# Connectors.net
KiCad netlist of a schematic drawn in Altium Designer
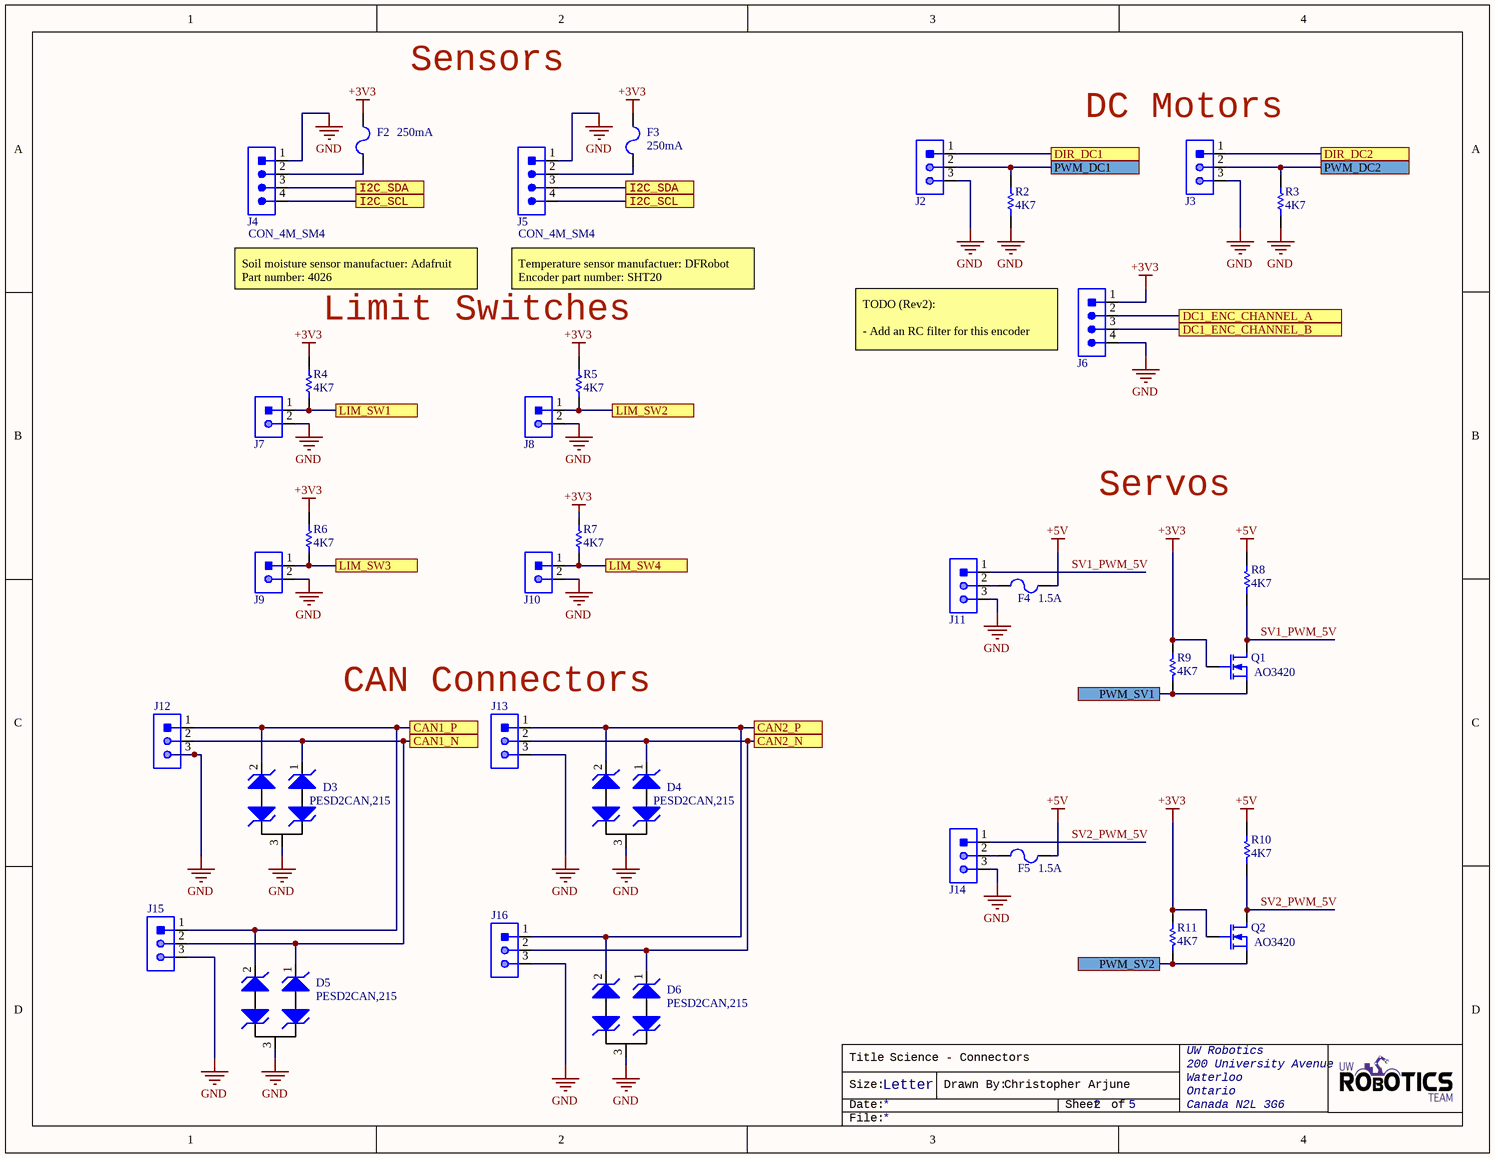
[diagram p0: Connectors.SchDoc]

(export (version "E")
  (design (tool "Eeschema 10.0.6"))
  (components
    (comp (ref "D3")
      (value "TVS_DIODE_CAN")
      (footprint "TVS_DIODE_CAN")
      (description "TVS DIODE 24V 41V SOT323-3")
      (fields
        (field (name "MANUFACTURER") "Nexperia USA Inc.")
        (field (name "MANUFACTURER PART NUMBER") "PESD2CAN,215")
      )
      (libsource (lib "UWRT_Schematic_Library_2020") (part "TVS_DIODE_CAN"))
    )
    (comp (ref "D4")
      (value "TVS_DIODE_CAN")
      (footprint "TVS_DIODE_CAN")
      (description "TVS DIODE 24V 41V SOT323-3")
      (fields
        (field (name "MANUFACTURER") "Nexperia USA Inc.")
        (field (name "MANUFACTURER PART NUMBER") "PESD2CAN,215")
      )
      (libsource (lib "UWRT_Schematic_Library_2020") (part "TVS_DIODE_CAN"))
    )
    (comp (ref "D5")
      (value "TVS_DIODE_CAN")
      (footprint "TVS_DIODE_CAN")
      (description "TVS DIODE 24V 41V SOT323-3")
      (fields
        (field (name "MANUFACTURER") "Nexperia USA Inc.")
        (field (name "MANUFACTURER PART NUMBER") "PESD2CAN,215")
      )
      (libsource (lib "UWRT_Schematic_Library_2020") (part "TVS_DIODE_CAN"))
    )
    (comp (ref "D6")
      (value "TVS_DIODE_CAN")
      (footprint "TVS_DIODE_CAN")
      (description "TVS DIODE 24V 41V SOT323-3")
      (fields
        (field (name "MANUFACTURER") "Nexperia USA Inc.")
        (field (name "MANUFACTURER PART NUMBER") "PESD2CAN,215")
      )
      (libsource (lib "UWRT_Schematic_Library_2020") (part "TVS_DIODE_CAN"))
    )
    (comp (ref "F2")
      (value "FUSE_250mA_0603")
      (footprint "FUSE_0603")
      (description "FUSE SMD 250mA 32V")
      (fields (field (name "CURRENT RATING") "250mA"))
      (libsource (lib "UWRT_Schematic_Library_2020") (part "FUSE_250mA_0603"))
    )
    (comp (ref "F3")
      (value "FUSE_250mA_0603")
      (footprint "FUSE_0603")
      (description "FUSE SMD 250mA 32V")
      (fields (field (name "CURRENT RATING") "250mA"))
      (libsource (lib "UWRT_Schematic_Library_2020") (part "FUSE_250mA_0603"))
    )
    (comp (ref "F4")
      (value "FUSE_1.5A_0603")
      (footprint "FUSE_0603")
      (description "FUSE SMD 1.5A 32V")
      (fields (field (name "CURRENT RATING") "1.5A"))
      (libsource (lib "UWRT_Schematic_Library_2020") (part "FUSE_1.5A_0603"))
    )
    (comp (ref "F5")
      (value "FUSE_1.5A_0603")
      (footprint "FUSE_0603")
      (description "FUSE SMD 1.5A 32V")
      (fields (field (name "CURRENT RATING") "1.5A"))
      (libsource (lib "UWRT_Schematic_Library_2020") (part "FUSE_1.5A_0603"))
    )
    (comp (ref "J2")
      (value "CON_3M_SM4")
      (footprint "JST-B3B-SM4-TB")
      (description "CONN HEADER SMD 3POS 2MM")
      (fields
        (field (name "MANUFACTURER") "JST")
        (field (name "MANUFACTURER PART NUMBER") "B3B-PH-SM4-TB(LF)(SN)")
      )
      (libsource (lib "UWRT_Schematic_Library_2020") (part "CON_3M_SM4"))
    )
    (comp (ref "J3")
      (value "CON_3M_SM4")
      (footprint "JST-B3B-SM4-TB")
      (description "CONN HEADER SMD 3POS 2MM")
      (fields
        (field (name "MANUFACTURER") "JST")
        (field (name "MANUFACTURER PART NUMBER") "B3B-PH-SM4-TB(LF)(SN)")
      )
      (libsource (lib "UWRT_Schematic_Library_2020") (part "CON_3M_SM4"))
    )
    (comp (ref "J4")
      (value "CON_4M_SM4")
      (footprint "JST-B4B-SM4-TB")
      (description "CONN HEADER SMD 4POS 2MM")
      (fields
        (field (name "MANUFACTURER") "JST")
        (field (name "MANUFACTURER PART NUMBER") "B4B-PH-SM4-TB(LF)(SN)")
      )
      (libsource (lib "UWRT_Schematic_Library_2020") (part "CON_4M_SM4"))
    )
    (comp (ref "J5")
      (value "CON_4M_SM4")
      (footprint "JST-B4B-SM4-TB")
      (description "CONN HEADER SMD 4POS 2MM")
      (fields
        (field (name "MANUFACTURER") "JST")
        (field (name "MANUFACTURER PART NUMBER") "B4B-PH-SM4-TB(LF)(SN)")
      )
      (libsource (lib "UWRT_Schematic_Library_2020") (part "CON_4M_SM4"))
    )
    (comp (ref "J6")
      (value "CON_4M_SM4")
      (footprint "JST-B4B-SM4-TB")
      (description "CONN HEADER SMD 4POS 2MM")
      (fields
        (field (name "MANUFACTURER") "JST")
        (field (name "MANUFACTURER PART NUMBER") "B4B-PH-SM4-TB(LF)(SN)")
      )
      (libsource (lib "UWRT_Schematic_Library_2020") (part "CON_4M_SM4"))
    )
    (comp (ref "J7")
      (value "CON_2M_SM4")
      (footprint "JST-B2B-SM4-TB")
      (description "CONN HEADER SMD 2POS 2MM")
      (fields
        (field (name "MANUFACTURER") "JST")
        (field (name "MANUFACTURER PART NUMBER") "B2B-PH-SM4-TB(LF)(SN)")
      )
      (libsource (lib "UWRT_Schematic_Library_2020") (part "CON_2M_SM4"))
    )
    (comp (ref "J8")
      (value "CON_2M_SM4")
      (footprint "JST-B2B-SM4-TB")
      (description "CONN HEADER SMD 2POS 2MM")
      (fields
        (field (name "MANUFACTURER") "JST")
        (field (name "MANUFACTURER PART NUMBER") "B2B-PH-SM4-TB(LF)(SN)")
      )
      (libsource (lib "UWRT_Schematic_Library_2020") (part "CON_2M_SM4"))
    )
    (comp (ref "J9")
      (value "CON_2M_SM4")
      (footprint "JST-B2B-SM4-TB")
      (description "CONN HEADER SMD 2POS 2MM")
      (fields
        (field (name "MANUFACTURER") "JST")
        (field (name "MANUFACTURER PART NUMBER") "B2B-PH-SM4-TB(LF)(SN)")
      )
      (libsource (lib "UWRT_Schematic_Library_2020") (part "CON_2M_SM4"))
    )
    (comp (ref "J10")
      (value "CON_2M_SM4")
      (footprint "JST-B2B-SM4-TB")
      (description "CONN HEADER SMD 2POS 2MM")
      (fields
        (field (name "MANUFACTURER") "JST")
        (field (name "MANUFACTURER PART NUMBER") "B2B-PH-SM4-TB(LF)(SN)")
      )
      (libsource (lib "UWRT_Schematic_Library_2020") (part "CON_2M_SM4"))
    )
    (comp (ref "J11")
      (value "CON_3M_SM4")
      (footprint "JST-B3B-SM4-TB")
      (description "CONN HEADER SMD 3POS 2MM")
      (fields
        (field (name "MANUFACTURER") "JST")
        (field (name "MANUFACTURER PART NUMBER") "B3B-PH-SM4-TB(LF)(SN)")
      )
      (libsource (lib "UWRT_Schematic_Library_2020") (part "CON_3M_SM4"))
    )
    (comp (ref "J12")
      (value "CON_3M_SM4")
      (footprint "JST-B3B-SM4-TB")
      (description "CONN HEADER SMD 3POS 2MM")
      (fields
        (field (name "MANUFACTURER") "JST")
        (field (name "MANUFACTURER PART NUMBER") "B3B-PH-SM4-TB(LF)(SN)")
      )
      (libsource (lib "UWRT_Schematic_Library_2020") (part "CON_3M_SM4"))
    )
    (comp (ref "J13")
      (value "CON_3M_SM4")
      (footprint "JST-B3B-SM4-TB")
      (description "CONN HEADER SMD 3POS 2MM")
      (fields
        (field (name "MANUFACTURER") "JST")
        (field (name "MANUFACTURER PART NUMBER") "B3B-PH-SM4-TB(LF)(SN)")
      )
      (libsource (lib "UWRT_Schematic_Library_2020") (part "CON_3M_SM4"))
    )
    (comp (ref "J14")
      (value "CON_3M_SM4")
      (footprint "JST-B3B-SM4-TB")
      (description "CONN HEADER SMD 3POS 2MM")
      (fields
        (field (name "MANUFACTURER") "JST")
        (field (name "MANUFACTURER PART NUMBER") "B3B-PH-SM4-TB(LF)(SN)")
      )
      (libsource (lib "UWRT_Schematic_Library_2020") (part "CON_3M_SM4"))
    )
    (comp (ref "J15")
      (value "CON_3M_SM4")
      (footprint "JST-B3B-SM4-TB")
      (description "CONN HEADER SMD 3POS 2MM")
      (fields
        (field (name "MANUFACTURER") "JST")
        (field (name "MANUFACTURER PART NUMBER") "B3B-PH-SM4-TB(LF)(SN)")
      )
      (libsource (lib "UWRT_Schematic_Library_2020") (part "CON_3M_SM4"))
    )
    (comp (ref "J16")
      (value "CON_3M_SM4")
      (footprint "JST-B3B-SM4-TB")
      (description "CONN HEADER SMD 3POS 2MM")
      (fields
        (field (name "MANUFACTURER") "JST")
        (field (name "MANUFACTURER PART NUMBER") "B3B-PH-SM4-TB(LF)(SN)")
      )
      (libsource (lib "UWRT_Schematic_Library_2020") (part "CON_3M_SM4"))
    )
    (comp (ref "Q1")
      (value "NMOS_20V_6A")
      (footprint "NMOS_SOT23-3")
      (description "MOSFET N-CH 20V 6A SOT23")
      (fields (field (name "MPN") "AO3420") (field (name "MANUFACTURER") "Alpha & Omega"))
      (libsource (lib "UWRT_Schematic_Library_2020") (part "NMOS_20V_6A"))
    )
    (comp (ref "Q2")
      (value "NMOS_20V_6A")
      (footprint "NMOS_SOT23-3")
      (description "MOSFET N-CH 20V 6A SOT23")
      (fields (field (name "MPN") "AO3420") (field (name "MANUFACTURER") "Alpha & Omega"))
      (libsource (lib "UWRT_Schematic_Library_2020") (part "NMOS_20V_6A"))
    )
    (comp (ref "R2")
      (value "4K7")
      (footprint "RESC0603(1608)_N")
      (description "RES SMD 4.7K OHM 5% 1/10W 0603")
      (fields (field (name "MANUFACTURER") "Yageo") (field (name "MPN") "RC0603JR-074K7L"))
      (libsource (lib "UWRT_Schematic_Library_2020") (part "RES_4K7_0603"))
    )
    (comp (ref "R3")
      (value "4K7")
      (footprint "RESC0603(1608)_N")
      (description "RES SMD 4.7K OHM 5% 1/10W 0603")
      (fields (field (name "MANUFACTURER") "Yageo") (field (name "MPN") "RC0603JR-074K7L"))
      (libsource (lib "UWRT_Schematic_Library_2020") (part "RES_4K7_0603"))
    )
    (comp (ref "R4")
      (value "4K7")
      (footprint "RESC0603(1608)_N")
      (description "RES SMD 4.7K OHM 5% 1/10W 0603")
      (fields (field (name "MANUFACTURER") "Yageo") (field (name "MPN") "RC0603JR-074K7L"))
      (libsource (lib "UWRT_Schematic_Library_2020") (part "RES_4K7_0603"))
    )
    (comp (ref "R5")
      (value "4K7")
      (footprint "RESC0603(1608)_N")
      (description "RES SMD 4.7K OHM 5% 1/10W 0603")
      (fields (field (name "MANUFACTURER") "Yageo") (field (name "MPN") "RC0603JR-074K7L"))
      (libsource (lib "UWRT_Schematic_Library_2020") (part "RES_4K7_0603"))
    )
    (comp (ref "R6")
      (value "4K7")
      (footprint "RESC0603(1608)_N")
      (description "RES SMD 4.7K OHM 5% 1/10W 0603")
      (fields (field (name "MANUFACTURER") "Yageo") (field (name "MPN") "RC0603JR-074K7L"))
      (libsource (lib "UWRT_Schematic_Library_2020") (part "RES_4K7_0603"))
    )
    (comp (ref "R7")
      (value "4K7")
      (footprint "RESC0603(1608)_N")
      (description "RES SMD 4.7K OHM 5% 1/10W 0603")
      (fields (field (name "MANUFACTURER") "Yageo") (field (name "MPN") "RC0603JR-074K7L"))
      (libsource (lib "UWRT_Schematic_Library_2020") (part "RES_4K7_0603"))
    )
    (comp (ref "R8")
      (value "4K7")
      (footprint "RESC0603(1608)_N")
      (description "RES SMD 4.7K OHM 5% 1/10W 0603")
      (fields (field (name "MANUFACTURER") "Yageo") (field (name "MPN") "RC0603JR-074K7L"))
      (libsource (lib "UWRT_Schematic_Library_2020") (part "RES_4K7_0603"))
    )
    (comp (ref "R9")
      (value "4K7")
      (footprint "RESC0603(1608)_N")
      (description "RES SMD 4.7K OHM 5% 1/10W 0603")
      (fields (field (name "MANUFACTURER") "Yageo") (field (name "MPN") "RC0603JR-074K7L"))
      (libsource (lib "UWRT_Schematic_Library_2020") (part "RES_4K7_0603"))
    )
    (comp (ref "R10")
      (value "4K7")
      (footprint "RESC0603(1608)_N")
      (description "RES SMD 4.7K OHM 5% 1/10W 0603")
      (fields (field (name "MANUFACTURER") "Yageo") (field (name "MPN") "RC0603JR-074K7L"))
      (libsource (lib "UWRT_Schematic_Library_2020") (part "RES_4K7_0603"))
    )
    (comp (ref "R11")
      (value "4K7")
      (footprint "RESC0603(1608)_N")
      (description "RES SMD 4.7K OHM 5% 1/10W 0603")
      (fields (field (name "MANUFACTURER") "Yageo") (field (name "MPN") "RC0603JR-074K7L"))
      (libsource (lib "UWRT_Schematic_Library_2020") (part "RES_4K7_0603"))
    )
  )
  (nets
    (net (code "1") (name "+3V3") (class "Default")
      (node (ref "F2") (pin "1") (pinfunction "1_1") (pintype "passive"))
      (node (ref "F3") (pin "1") (pinfunction "1_1") (pintype "passive"))
      (node (ref "J6") (pin "1") (pinfunction "1_1") (pintype "passive"))
      (node (ref "Q1") (pin "1") (pinfunction "G_1") (pintype "passive"))
      (node (ref "Q2") (pin "1") (pinfunction "G_1") (pintype "passive"))
      (node (ref "R11") (pin "2") (pinfunction "2_2") (pintype "passive"))
      (node (ref "R4") (pin "2") (pinfunction "2_2") (pintype "passive"))
      (node (ref "R5") (pin "2") (pinfunction "2_2") (pintype "passive"))
      (node (ref "R6") (pin "2") (pinfunction "2_2") (pintype "passive"))
      (node (ref "R7") (pin "2") (pinfunction "2_2") (pintype "passive"))
      (node (ref "R9") (pin "2") (pinfunction "2_2") (pintype "passive"))
    )
    (net (code "2") (name "+5V") (class "Default")
      (node (ref "F4") (pin "1") (pinfunction "1_1") (pintype "passive"))
      (node (ref "F5") (pin "1") (pinfunction "1_1") (pintype "passive"))
      (node (ref "R10") (pin "2") (pinfunction "2_2") (pintype "passive"))
      (node (ref "R8") (pin "2") (pinfunction "2_2") (pintype "passive"))
    )
    (net (code "3") (name "/CAN1_N") (class "Default")
      (node (ref "D3") (pin "1") (pinfunction "1_1") (pintype "passive"))
      (node (ref "D5") (pin "1") (pinfunction "1_1") (pintype "passive"))
      (node (ref "J12") (pin "2") (pinfunction "2_2") (pintype "passive"))
      (node (ref "J15") (pin "2") (pinfunction "2_2") (pintype "passive"))
    )
    (net (code "4") (name "/CAN1_P") (class "Default")
      (node (ref "D3") (pin "2") (pinfunction "2_2") (pintype "passive"))
      (node (ref "D5") (pin "2") (pinfunction "2_2") (pintype "passive"))
      (node (ref "J12") (pin "1") (pinfunction "1_1") (pintype "passive"))
      (node (ref "J15") (pin "1") (pinfunction "1_1") (pintype "passive"))
    )
    (net (code "5") (name "/CAN2_N") (class "Default")
      (node (ref "D4") (pin "1") (pinfunction "1_1") (pintype "passive"))
      (node (ref "D6") (pin "1") (pinfunction "1_1") (pintype "passive"))
      (node (ref "J13") (pin "2") (pinfunction "2_2") (pintype "passive"))
      (node (ref "J16") (pin "2") (pinfunction "2_2") (pintype "passive"))
    )
    (net (code "6") (name "/CAN2_P") (class "Default")
      (node (ref "D4") (pin "2") (pinfunction "2_2") (pintype "passive"))
      (node (ref "D6") (pin "2") (pinfunction "2_2") (pintype "passive"))
      (node (ref "J13") (pin "1") (pinfunction "1_1") (pintype "passive"))
      (node (ref "J16") (pin "1") (pinfunction "1_1") (pintype "passive"))
    )
    (net (code "7") (name "/DC1_ENC_CHANNEL_A") (class "Default")
      (node (ref "J6") (pin "2") (pinfunction "2_2") (pintype "passive"))
    )
    (net (code "8") (name "/DC1_ENC_CHANNEL_B") (class "Default")
      (node (ref "J6") (pin "3") (pinfunction "3_3") (pintype "passive"))
    )
    (net (code "9") (name "/DIR_DC1") (class "Default")
      (node (ref "J2") (pin "1") (pinfunction "1_1") (pintype "passive"))
    )
    (net (code "10") (name "/DIR_DC2") (class "Default")
      (node (ref "J3") (pin "1") (pinfunction "1_1") (pintype "passive"))
    )
    (net (code "11") (name "/I2C_SCL") (class "Default")
      (node (ref "J4") (pin "4") (pinfunction "4_4") (pintype "passive"))
      (node (ref "J5") (pin "4") (pinfunction "4_4") (pintype "passive"))
    )
    (net (code "12") (name "/I2C_SDA") (class "Default")
      (node (ref "J4") (pin "3") (pinfunction "3_3") (pintype "passive"))
      (node (ref "J5") (pin "3") (pinfunction "3_3") (pintype "passive"))
    )
    (net (code "13") (name "/LIM_SW1") (class "Default")
      (node (ref "J7") (pin "1") (pinfunction "1_1") (pintype "passive"))
      (node (ref "R4") (pin "1") (pinfunction "1_1") (pintype "passive"))
    )
    (net (code "14") (name "/LIM_SW2") (class "Default")
      (node (ref "J8") (pin "1") (pinfunction "1_1") (pintype "passive"))
      (node (ref "R5") (pin "1") (pinfunction "1_1") (pintype "passive"))
    )
    (net (code "15") (name "/LIM_SW3") (class "Default")
      (node (ref "J9") (pin "1") (pinfunction "1_1") (pintype "passive"))
      (node (ref "R6") (pin "1") (pinfunction "1_1") (pintype "passive"))
    )
    (net (code "16") (name "/LIM_SW4") (class "Default")
      (node (ref "J10") (pin "1") (pinfunction "1_1") (pintype "passive"))
      (node (ref "R7") (pin "1") (pinfunction "1_1") (pintype "passive"))
    )
    (net (code "17") (name "/PWM_DC1") (class "Default")
      (node (ref "J2") (pin "2") (pinfunction "2_2") (pintype "passive"))
      (node (ref "R2") (pin "1") (pinfunction "1_1") (pintype "passive"))
    )
    (net (code "18") (name "/PWM_DC2") (class "Default")
      (node (ref "J3") (pin "2") (pinfunction "2_2") (pintype "passive"))
      (node (ref "R3") (pin "1") (pinfunction "1_1") (pintype "passive"))
    )
    (net (code "19") (name "/PWM_SV1") (class "Default")
      (node (ref "Q1") (pin "2") (pinfunction "S_2") (pintype "passive"))
      (node (ref "R9") (pin "1") (pinfunction "1_1") (pintype "passive"))
    )
    (net (code "20") (name "/PWM_SV2") (class "Default")
      (node (ref "Q2") (pin "2") (pinfunction "S_2") (pintype "passive"))
      (node (ref "R11") (pin "1") (pinfunction "1_1") (pintype "passive"))
    )
    (net (code "21") (name "/SV1_PWM_5V") (class "Default")
      (node (ref "J11") (pin "1") (pinfunction "1_1") (pintype "passive"))
      (node (ref "Q1") (pin "3") (pinfunction "D_3") (pintype "passive"))
      (node (ref "R8") (pin "1") (pinfunction "1_1") (pintype "passive"))
    )
    (net (code "22") (name "/SV2_PWM_5V") (class "Default")
      (node (ref "J14") (pin "1") (pinfunction "1_1") (pintype "passive"))
      (node (ref "Q2") (pin "3") (pinfunction "D_3") (pintype "passive"))
      (node (ref "R10") (pin "1") (pinfunction "1_1") (pintype "passive"))
    )
    (net (code "23") (name "GND") (class "Default")
      (node (ref "D3") (pin "3") (pinfunction "3_3") (pintype "passive"))
      (node (ref "D4") (pin "3") (pinfunction "3_3") (pintype "passive"))
      (node (ref "D5") (pin "3") (pinfunction "3_3") (pintype "passive"))
      (node (ref "D6") (pin "3") (pinfunction "3_3") (pintype "passive"))
      (node (ref "J10") (pin "2") (pinfunction "2_2") (pintype "passive"))
      (node (ref "J11") (pin "3") (pinfunction "3_3") (pintype "passive"))
      (node (ref "J12") (pin "3") (pinfunction "3_3") (pintype "passive"))
      (node (ref "J13") (pin "3") (pinfunction "3_3") (pintype "passive"))
      (node (ref "J14") (pin "3") (pinfunction "3_3") (pintype "passive"))
      (node (ref "J15") (pin "3") (pinfunction "3_3") (pintype "passive"))
      (node (ref "J16") (pin "3") (pinfunction "3_3") (pintype "passive"))
      (node (ref "J2") (pin "3") (pinfunction "3_3") (pintype "passive"))
      (node (ref "J3") (pin "3") (pinfunction "3_3") (pintype "passive"))
      (node (ref "J4") (pin "1") (pinfunction "1_1") (pintype "passive"))
      (node (ref "J5") (pin "1") (pinfunction "1_1") (pintype "passive"))
      (node (ref "J6") (pin "4") (pinfunction "4_4") (pintype "passive"))
      (node (ref "J7") (pin "2") (pinfunction "2_2") (pintype "passive"))
      (node (ref "J8") (pin "2") (pinfunction "2_2") (pintype "passive"))
      (node (ref "J9") (pin "2") (pinfunction "2_2") (pintype "passive"))
      (node (ref "R2") (pin "2") (pinfunction "2_2") (pintype "passive"))
      (node (ref "R3") (pin "2") (pinfunction "2_2") (pintype "passive"))
    )
    (net (code "24") (name "Net-(F2-Pad2)") (class "Default")
      (node (ref "F2") (pin "2") (pinfunction "2_2") (pintype "passive"))
      (node (ref "J4") (pin "2") (pinfunction "2_2") (pintype "passive"))
    )
    (net (code "25") (name "Net-(F3-Pad2)") (class "Default")
      (node (ref "F3") (pin "2") (pinfunction "2_2") (pintype "passive"))
      (node (ref "J5") (pin "2") (pinfunction "2_2") (pintype "passive"))
    )
    (net (code "26") (name "Net-(F4-Pad2)") (class "Default")
      (node (ref "F4") (pin "2") (pinfunction "2_2") (pintype "passive"))
      (node (ref "J11") (pin "2") (pinfunction "2_2") (pintype "passive"))
    )
    (net (code "27") (name "Net-(F5-Pad2)") (class "Default")
      (node (ref "F5") (pin "2") (pinfunction "2_2") (pintype "passive"))
      (node (ref "J14") (pin "2") (pinfunction "2_2") (pintype "passive"))
    )
  )
)
